# well-siting-meter.net
KiCad netlist of a schematic drawn in EAGLE
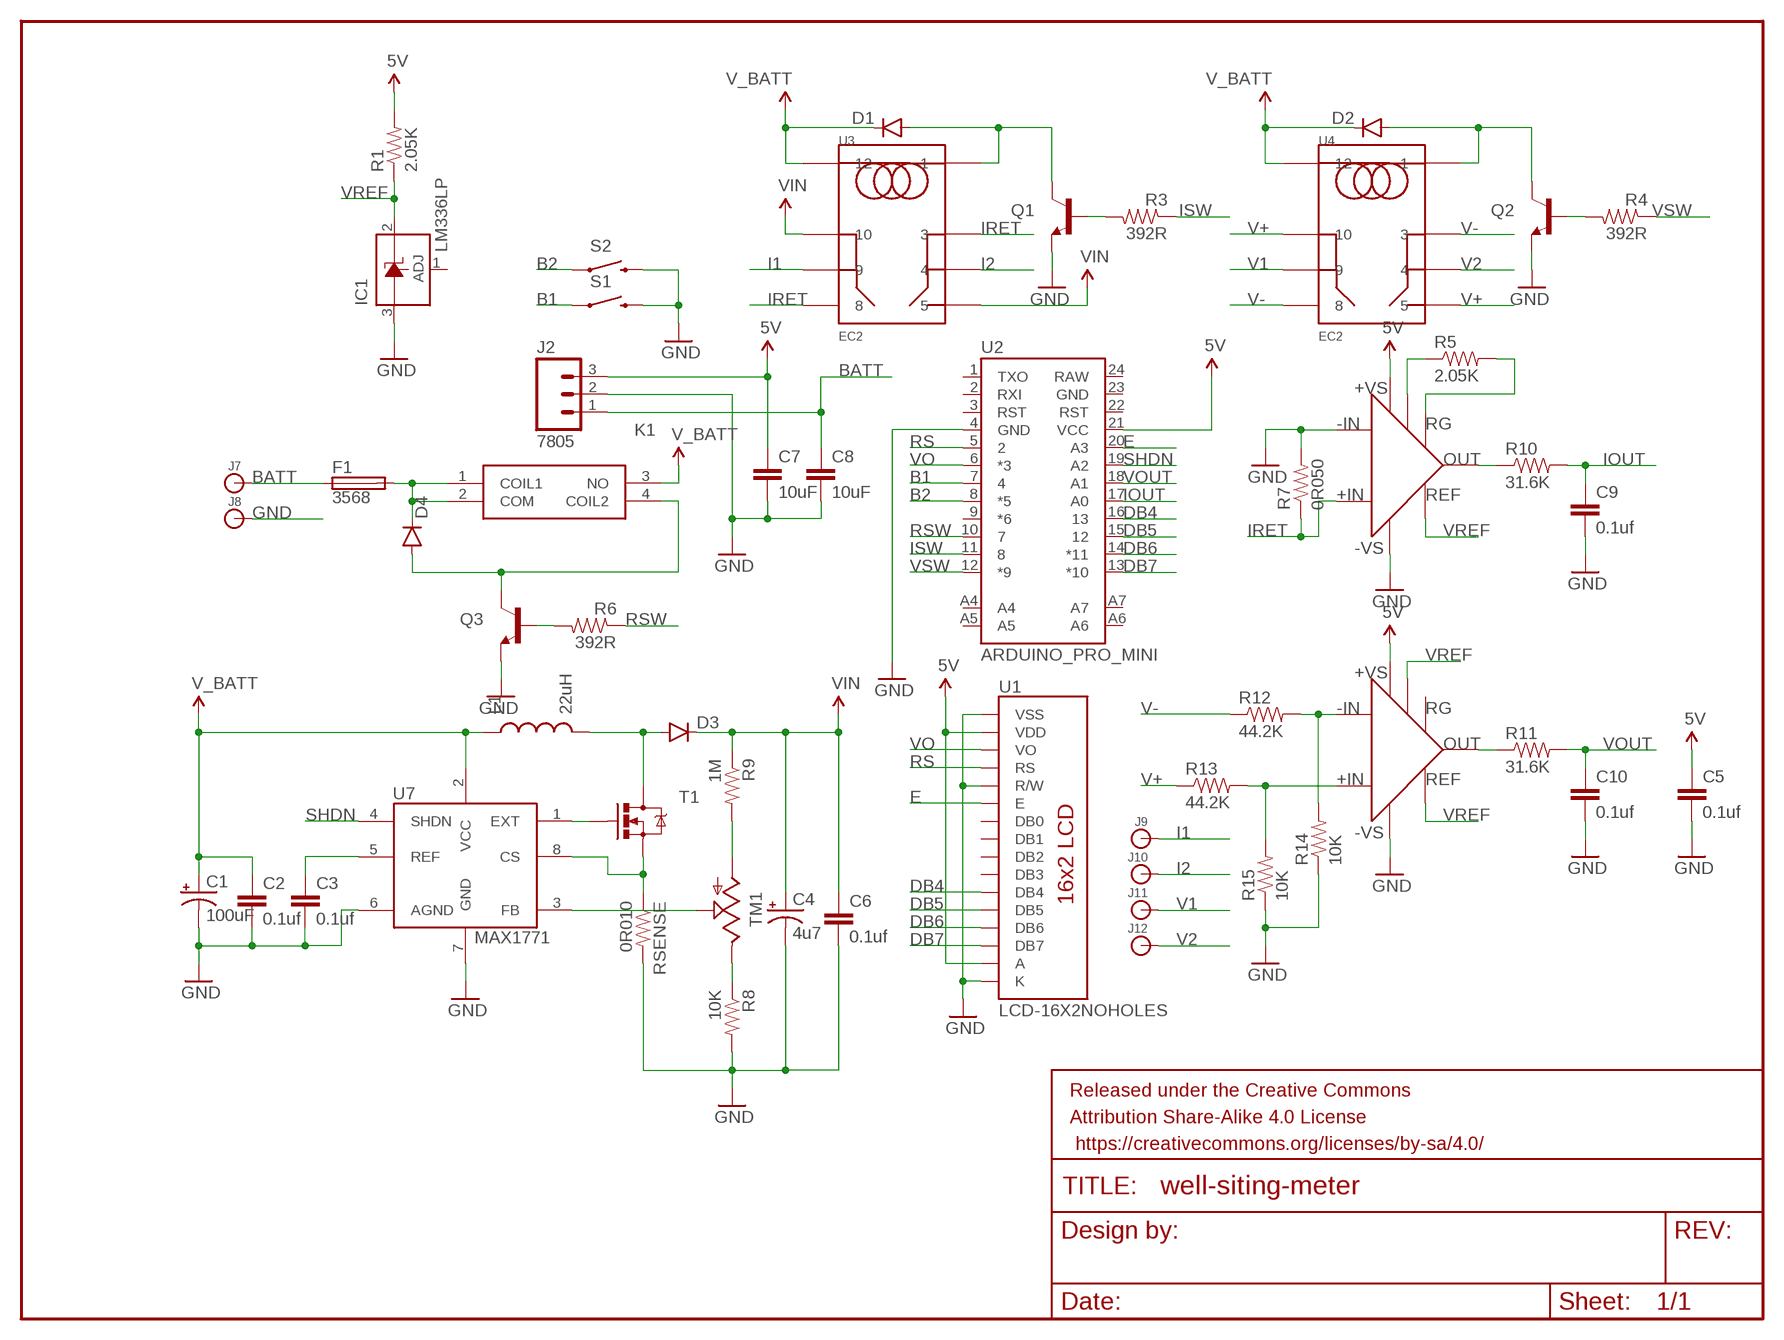
[diagram p0: schematic, sheet 1]

(export (version "E")
  (design (tool "Eeschema 10.0.6"))
  (components
    (comp (ref "C1")
      (value "100uF")
      (footprint "eagle-import:CPOL-RADIAL-1000UF-25V")
      (libsource (lib "eagle-import") (part "CAP_POLPTH4"))
    )
    (comp (ref "C2")
      (value "0.1uf")
      (footprint "eagle-import:CAP-PTH-5MM")
      (libsource (lib "eagle-import") (part "CAPPTH1"))
    )
    (comp (ref "C3")
      (value "0.1uf")
      (footprint "eagle-import:CAP-PTH-5MM")
      (libsource (lib "eagle-import") (part "CAPPTH1"))
    )
    (comp (ref "C4")
      (value "4u7")
      (footprint "eagle-import:CPOL-RADIAL-1000UF-25V")
      (libsource (lib "eagle-import") (part "CAP_POLPTH4"))
    )
    (comp (ref "C5")
      (value "0.1uf")
      (footprint "eagle-import:CAP-PTH-5MM")
      (libsource (lib "eagle-import") (part "CAPPTH1"))
    )
    (comp (ref "C6")
      (value "0.1uf")
      (footprint "eagle-import:CAP-PTH-5MM")
      (libsource (lib "eagle-import") (part "CAPPTH1"))
    )
    (comp (ref "C7")
      (value "10uF")
      (footprint "eagle-import:CAP-PTH-5MM")
      (libsource (lib "eagle-import") (part "CAPPTH1"))
    )
    (comp (ref "C8")
      (value "10uF")
      (footprint "eagle-import:CAP-PTH-5MM")
      (libsource (lib "eagle-import") (part "CAPPTH1"))
    )
    (comp (ref "C9")
      (value "0.1uf")
      (footprint "eagle-import:CAP-PTH-5MM")
      (libsource (lib "eagle-import") (part "CAPPTH1"))
    )
    (comp (ref "C10")
      (value "0.1uf")
      (footprint "eagle-import:CAP-PTH-5MM")
      (libsource (lib "eagle-import") (part "CAPPTH1"))
    )
    (comp (ref "D1")
      (value "DIODEPTH")
      (footprint "eagle-import:DIODE-1N4001")
      (libsource (lib "eagle-import") (part "DIODEPTH"))
    )
    (comp (ref "D2")
      (value "DIODEPTH")
      (footprint "eagle-import:DIODE-1N4001")
      (libsource (lib "eagle-import") (part "DIODEPTH"))
    )
    (comp (ref "D3")
      (value "DIODEPTH")
      (footprint "eagle-import:DIODE-1N4001")
      (libsource (lib "eagle-import") (part "DIODEPTH"))
    )
    (comp (ref "D4")
      (value "DIODEPTH")
      (footprint "eagle-import:DIODE-1N4001")
      (libsource (lib "eagle-import") (part "DIODEPTH"))
    )
    (comp (ref "F1")
      (value "3568")
      (footprint "eagle-import:3568")
      (libsource (lib "eagle-import") (part "3568"))
    )
    (comp (ref "FRAME1")
      (value "FRAME-LETTER")
      (footprint "eagle-import:CREATIVE_COMMONS")
      (libsource (lib "eagle-import") (part "FRAME-LETTER"))
    )
    (comp (ref "IC1")
      (value "LM336LP")
      (footprint "eagle-import:TO92")
      (libsource (lib "eagle-import") (part "LM336LP"))
    )
    (comp (ref "J2")
      (value "7805")
      (footprint "eagle-import:1X03")
      (libsource (lib "eagle-import") (part "M03PTH"))
    )
    (comp (ref "J7")
      (value "BANANA_CONN")
      (footprint "eagle-import:BANANA_CONN")
      (libsource (lib "eagle-import") (part "BANANA_CONN"))
    )
    (comp (ref "J8")
      (value "BANANA_CONN")
      (footprint "eagle-import:BANANA_CONN")
      (libsource (lib "eagle-import") (part "BANANA_CONN"))
    )
    (comp (ref "J9")
      (value "BANANA_CONN")
      (footprint "eagle-import:BANANA_CONN")
      (libsource (lib "eagle-import") (part "BANANA_CONN"))
    )
    (comp (ref "J10")
      (value "BANANA_CONN")
      (footprint "eagle-import:BANANA_CONN")
      (libsource (lib "eagle-import") (part "BANANA_CONN"))
    )
    (comp (ref "J11")
      (value "BANANA_CONN")
      (footprint "eagle-import:BANANA_CONN")
      (libsource (lib "eagle-import") (part "BANANA_CONN"))
    )
    (comp (ref "J12")
      (value "BANANA_CONN")
      (footprint "eagle-import:BANANA_CONN")
      (libsource (lib "eagle-import") (part "BANANA_CONN"))
    )
    (comp (ref "K1")
      (value "OJE-SH-105HM,000")
      (footprint "eagle-import:OJ-SH-124LMH")
      (fields (field (name "RS_PART_NUMBER") "1639319"))
      (libsource (lib "eagle-import") (part "OJE-SH-105HM,000"))
    )
    (comp (ref "L1")
      (value "22uH")
      (footprint "eagle-import:1415")
      (libsource (lib "eagle-import") (part "WE-FAMI"))
    )
    (comp (ref "Q1")
      (value "TRANSISTOR_NPNTO92")
      (footprint "eagle-import:TO-92")
      (libsource (lib "eagle-import") (part "TRANSISTOR_NPNTO92"))
    )
    (comp (ref "Q2")
      (value "TRANSISTOR_NPNTO92")
      (footprint "eagle-import:TO-92")
      (libsource (lib "eagle-import") (part "TRANSISTOR_NPNTO92"))
    )
    (comp (ref "Q3")
      (value "TRANSISTOR_NPNTO92")
      (footprint "eagle-import:TO-92")
      (libsource (lib "eagle-import") (part "TRANSISTOR_NPNTO92"))
    )
    (comp (ref "R1")
      (value "2.05K")
      (footprint "eagle-import:AXIAL-0.4")
      (libsource (lib "eagle-import") (part "RESISTORPTH-1/4W"))
    )
    (comp (ref "R3")
      (value "392R")
      (footprint "eagle-import:AXIAL-0.4")
      (libsource (lib "eagle-import") (part "RESISTORPTH-1/4W"))
    )
    (comp (ref "R4")
      (value "392R")
      (footprint "eagle-import:AXIAL-0.4")
      (libsource (lib "eagle-import") (part "RESISTORPTH-1/4W"))
    )
    (comp (ref "R5")
      (value "2.05K")
      (footprint "eagle-import:AXIAL-0.4")
      (libsource (lib "eagle-import") (part "RESISTORPTH-1/4W"))
    )
    (comp (ref "R6")
      (value "392R")
      (footprint "eagle-import:AXIAL-0.4")
      (libsource (lib "eagle-import") (part "RESISTORPTH-1/4W"))
    )
    (comp (ref "R7")
      (value "0R050")
      (footprint "eagle-import:AXIAL-0.6")
      (libsource (lib "eagle-import") (part "RESISTORPTH-1W"))
    )
    (comp (ref "R8")
      (value "10K")
      (footprint "eagle-import:AXIAL-0.4")
      (libsource (lib "eagle-import") (part "RESISTORPTH-1/4W"))
    )
    (comp (ref "R9")
      (value "1M")
      (footprint "eagle-import:AXIAL-0.4")
      (libsource (lib "eagle-import") (part "RESISTORPTH-1/4W"))
    )
    (comp (ref "R10")
      (value "31.6K")
      (footprint "eagle-import:AXIAL-0.4")
      (libsource (lib "eagle-import") (part "RESISTORPTH-1/4W"))
    )
    (comp (ref "R11")
      (value "31.6K")
      (footprint "eagle-import:AXIAL-0.4")
      (libsource (lib "eagle-import") (part "RESISTORPTH-1/4W"))
    )
    (comp (ref "R12")
      (value "44.2K")
      (footprint "eagle-import:AXIAL-0.4")
      (libsource (lib "eagle-import") (part "RESISTORPTH-1/4W"))
    )
    (comp (ref "R13")
      (value "44.2K")
      (footprint "eagle-import:AXIAL-0.4")
      (libsource (lib "eagle-import") (part "RESISTORPTH-1/4W"))
    )
    (comp (ref "R14")
      (value "10K")
      (footprint "eagle-import:AXIAL-0.4")
      (libsource (lib "eagle-import") (part "RESISTORPTH-1/4W"))
    )
    (comp (ref "R15")
      (value "10K")
      (footprint "eagle-import:AXIAL-0.4")
      (libsource (lib "eagle-import") (part "RESISTORPTH-1/4W"))
    )
    (comp (ref "RSENSE")
      (value "0R010")
      (footprint "eagle-import:AXIAL-0.6")
      (libsource (lib "eagle-import") (part "RESISTORPTH-1W"))
    )
    (comp (ref "S1")
      (value "SWITCH-MOMENTARY-2PTH")
      (footprint "eagle-import:TACTILE-PTH")
      (libsource (lib "eagle-import") (part "SWITCH-MOMENTARY-2PTH"))
    )
    (comp (ref "S2")
      (value "SWITCH-MOMENTARY-2PTH")
      (footprint "eagle-import:TACTILE-PTH")
      (libsource (lib "eagle-import") (part "SWITCH-MOMENTARY-2PTH"))
    )
    (comp (ref "T1")
      (value "MOSFET-NCHANNELFQP30N06L")
      (footprint "eagle-import:TO220V")
      (libsource (lib "eagle-import") (part "MOSFET-NCHANNELFQP30N06L"))
    )
    (comp (ref "TM1")
      (value "TRIM3386")
      (footprint "eagle-import:TRIM-3386")
      (libsource (lib "eagle-import") (part "TRIM3386"))
    )
    (comp (ref "U1")
      (value "LCD-16X2NOHOLES")
      (footprint "eagle-import:LCD-16X2_NOHOLES")
      (libsource (lib "eagle-import") (part "LCD-16X2NOHOLES"))
    )
    (comp (ref "U2")
      (value "ARDUINO_PRO_MINI")
      (footprint "eagle-import:ARDUINO_PRO_MINI")
      (libsource (lib "eagle-import") (part "ARDUINO_PRO_MINI"))
    )
    (comp (ref "U3")
      (value "EC2")
      (footprint "eagle-import:EC2")
      (libsource (lib "eagle-import") (part "EC2"))
    )
    (comp (ref "U4")
      (value "EC2")
      (footprint "eagle-import:EC2")
      (libsource (lib "eagle-import") (part "EC2"))
    )
    (comp (ref "U5")
      (value "AD623")
      (footprint "eagle-import:DIP08")
      (libsource (lib "eagle-import") (part "AD623"))
    )
    (comp (ref "U6")
      (value "AD629")
      (footprint "eagle-import:DIP08")
      (libsource (lib "eagle-import") (part "AD623"))
    )
    (comp (ref "U7")
      (value "MAX1771")
      (footprint "eagle-import:DIP-08")
      (libsource (lib "eagle-import") (part "MAX1771"))
    )
  )
  (nets
    (net (code "1") (name "/B1") (class "Default")
      (node (ref "S1") (pin "1") (pinfunction "1_1") (pintype "passive"))
      (node (ref "U2") (pin "7") (pinfunction "4_7") (pintype "bidirectional"))
    )
    (net (code "2") (name "/B2") (class "Default")
      (node (ref "S2") (pin "1") (pinfunction "1_1") (pintype "passive"))
      (node (ref "U2") (pin "8") (pinfunction "*5_8") (pintype "bidirectional"))
    )
    (net (code "3") (name "/BATT") (class "Default")
      (node (ref "C8") (pin "1") (pinfunction "1_1") (pintype "passive"))
      (node (ref "F1") (pin "1") (pinfunction "1_1") (pintype "passive"))
      (node (ref "F1") (pin "2") (pinfunction "1_2") (pintype "passive"))
      (node (ref "J2") (pin "1") (pinfunction "1_1") (pintype "passive"))
      (node (ref "J7") (pin "P$1") (pinfunction "1_P$1") (pintype "passive"))
    )
    (net (code "4") (name "/DB4") (class "Default")
      (node (ref "U1") (pin "11") (pinfunction "DB4_11") (pintype "bidirectional"))
      (node (ref "U2") (pin "16") (pinfunction "13_16") (pintype "bidirectional"))
    )
    (net (code "5") (name "/DB5") (class "Default")
      (node (ref "U1") (pin "12") (pinfunction "DB5_12") (pintype "bidirectional"))
      (node (ref "U2") (pin "15") (pinfunction "12_15") (pintype "bidirectional"))
    )
    (net (code "6") (name "/DB6") (class "Default")
      (node (ref "U1") (pin "13") (pinfunction "DB6_13") (pintype "bidirectional"))
      (node (ref "U2") (pin "14") (pinfunction "*11_14") (pintype "bidirectional"))
    )
    (net (code "7") (name "/DB7") (class "Default")
      (node (ref "U1") (pin "14") (pinfunction "DB7_14") (pintype "bidirectional"))
      (node (ref "U2") (pin "13") (pinfunction "*10_13") (pintype "bidirectional"))
    )
    (net (code "8") (name "/E") (class "Default")
      (node (ref "U1") (pin "6") (pinfunction "E_6") (pintype "input"))
      (node (ref "U2") (pin "20") (pinfunction "A3_20") (pintype "bidirectional"))
    )
    (net (code "9") (name "/I1") (class "Default")
      (node (ref "J9") (pin "P$1") (pinfunction "1_P$1") (pintype "passive"))
      (node (ref "U3") (pin "9") (pinfunction "9_9") (pintype "bidirectional"))
    )
    (net (code "10") (name "/I2") (class "Default")
      (node (ref "J10") (pin "P$1") (pinfunction "1_P$1") (pintype "passive"))
      (node (ref "U3") (pin "4") (pinfunction "4_4") (pintype "bidirectional"))
    )
    (net (code "11") (name "/IOUT") (class "Default")
      (node (ref "C9") (pin "1") (pinfunction "1_1") (pintype "passive"))
      (node (ref "R10") (pin "P$2") (pinfunction "2_P$2") (pintype "passive"))
      (node (ref "U2") (pin "17") (pinfunction "A0_17") (pintype "bidirectional"))
    )
    (net (code "12") (name "/IRET") (class "Default")
      (node (ref "R7") (pin "P$1") (pinfunction "1_P$1") (pintype "passive"))
      (node (ref "U3") (pin "3") (pinfunction "3_3") (pintype "bidirectional"))
      (node (ref "U3") (pin "8") (pinfunction "8_8") (pintype "bidirectional"))
      (node (ref "U5") (pin "3") (pinfunction "+IN_3") (pintype "bidirectional"))
    )
    (net (code "13") (name "/ISW") (class "Default")
      (node (ref "R3") (pin "P$1") (pinfunction "1_P$1") (pintype "passive"))
      (node (ref "U2") (pin "11") (pinfunction "8_11") (pintype "bidirectional"))
    )
    (net (code "14") (name "/RS") (class "Default")
      (node (ref "U1") (pin "4") (pinfunction "RS_4") (pintype "input"))
      (node (ref "U2") (pin "5") (pinfunction "2_5") (pintype "bidirectional"))
    )
    (net (code "15") (name "/RSW") (class "Default")
      (node (ref "R6") (pin "P$1") (pinfunction "1_P$1") (pintype "passive"))
      (node (ref "U2") (pin "10") (pinfunction "7_10") (pintype "bidirectional"))
    )
    (net (code "16") (name "/SHDN") (class "Default")
      (node (ref "U2") (pin "19") (pinfunction "A2_19") (pintype "bidirectional"))
      (node (ref "U7") (pin "4") (pinfunction "SHDN_4") (pintype "input"))
    )
    (net (code "17") (name "/V+") (class "Default")
      (node (ref "R13") (pin "P$1") (pinfunction "1_P$1") (pintype "passive"))
      (node (ref "U4") (pin "10") (pinfunction "10_10") (pintype "bidirectional"))
      (node (ref "U4") (pin "5") (pinfunction "5_5") (pintype "bidirectional"))
    )
    (net (code "18") (name "/V-") (class "Default")
      (node (ref "R12") (pin "P$1") (pinfunction "1_P$1") (pintype "passive"))
      (node (ref "U4") (pin "3") (pinfunction "3_3") (pintype "bidirectional"))
      (node (ref "U4") (pin "8") (pinfunction "8_8") (pintype "bidirectional"))
    )
    (net (code "19") (name "/V1") (class "Default")
      (node (ref "J11") (pin "P$1") (pinfunction "1_P$1") (pintype "passive"))
      (node (ref "U4") (pin "9") (pinfunction "9_9") (pintype "bidirectional"))
    )
    (net (code "20") (name "/V2") (class "Default")
      (node (ref "J12") (pin "P$1") (pinfunction "1_P$1") (pintype "passive"))
      (node (ref "U4") (pin "4") (pinfunction "4_4") (pintype "bidirectional"))
    )
    (net (code "21") (name "/VO") (class "Default")
      (node (ref "U1") (pin "3") (pinfunction "VO_3") (pintype "bidirectional"))
      (node (ref "U2") (pin "6") (pinfunction "*3_6") (pintype "bidirectional"))
    )
    (net (code "22") (name "/VOUT") (class "Default")
      (node (ref "C10") (pin "1") (pinfunction "1_1") (pintype "passive"))
      (node (ref "R11") (pin "P$2") (pinfunction "2_P$2") (pintype "passive"))
      (node (ref "U2") (pin "18") (pinfunction "A1_18") (pintype "bidirectional"))
    )
    (net (code "23") (name "/VREF") (class "Default")
      (node (ref "IC1") (pin "2") (pinfunction "C_2") (pintype "passive"))
      (node (ref "R1") (pin "P$1") (pinfunction "1_P$1") (pintype "passive"))
      (node (ref "U5") (pin "5") (pinfunction "REF_5") (pintype "bidirectional"))
      (node (ref "U6") (pin "1") (pinfunction "-RG_1") (pintype "bidirectional"))
      (node (ref "U6") (pin "5") (pinfunction "REF_5") (pintype "bidirectional"))
    )
    (net (code "24") (name "/VSW") (class "Default")
      (node (ref "R4") (pin "P$1") (pinfunction "1_P$1") (pintype "passive"))
      (node (ref "U2") (pin "12") (pinfunction "*9_12") (pintype "bidirectional"))
    )
    (net (code "25") (name "5V") (class "Default")
      (node (ref "C5") (pin "1") (pinfunction "1_1") (pintype "passive"))
      (node (ref "C7") (pin "1") (pinfunction "1_1") (pintype "passive"))
      (node (ref "J2") (pin "3") (pinfunction "3_3") (pintype "passive"))
      (node (ref "R1") (pin "P$2") (pinfunction "2_P$2") (pintype "passive"))
      (node (ref "U1") (pin "15") (pinfunction "A_15") (pintype "power_in"))
      (node (ref "U1") (pin "2") (pinfunction "VDD_2") (pintype "power_in"))
      (node (ref "U2") (pin "21") (pinfunction "VCC_21") (pintype "bidirectional"))
      (node (ref "U5") (pin "7") (pinfunction "+VS_7") (pintype "bidirectional"))
      (node (ref "U6") (pin "7") (pinfunction "+VS_7") (pintype "bidirectional"))
    )
    (net (code "26") (name "GND") (class "Default")
      (node (ref "C1") (pin "2") (pinfunction "-_2") (pintype "passive"))
      (node (ref "C10") (pin "2") (pinfunction "2_2") (pintype "passive"))
      (node (ref "C2") (pin "2") (pinfunction "2_2") (pintype "passive"))
      (node (ref "C3") (pin "2") (pinfunction "2_2") (pintype "passive"))
      (node (ref "C4") (pin "2") (pinfunction "-_2") (pintype "passive"))
      (node (ref "C5") (pin "2") (pinfunction "2_2") (pintype "passive"))
      (node (ref "C6") (pin "2") (pinfunction "2_2") (pintype "passive"))
      (node (ref "C7") (pin "2") (pinfunction "2_2") (pintype "passive"))
      (node (ref "C8") (pin "2") (pinfunction "2_2") (pintype "passive"))
      (node (ref "C9") (pin "2") (pinfunction "2_2") (pintype "passive"))
      (node (ref "IC1") (pin "3") (pinfunction "A_3") (pintype "input"))
      (node (ref "J2") (pin "2") (pinfunction "2_2") (pintype "passive"))
      (node (ref "J8") (pin "P$1") (pinfunction "1_P$1") (pintype "passive"))
      (node (ref "Q1") (pin "1") (pinfunction "E_1") (pintype "passive"))
      (node (ref "Q2") (pin "1") (pinfunction "E_1") (pintype "passive"))
      (node (ref "Q3") (pin "1") (pinfunction "E_1") (pintype "passive"))
      (node (ref "R14") (pin "P$1") (pinfunction "1_P$1") (pintype "passive"))
      (node (ref "R15") (pin "P$1") (pinfunction "1_P$1") (pintype "passive"))
      (node (ref "R7") (pin "P$2") (pinfunction "2_P$2") (pintype "passive"))
      (node (ref "R8") (pin "P$2") (pinfunction "2_P$2") (pintype "passive"))
      (node (ref "RSENSE") (pin "P$2") (pinfunction "2_P$2") (pintype "passive"))
      (node (ref "S1") (pin "3") (pinfunction "2_3") (pintype "passive"))
      (node (ref "S2") (pin "3") (pinfunction "2_3") (pintype "passive"))
      (node (ref "U1") (pin "1") (pinfunction "VSS_1") (pintype "power_in"))
      (node (ref "U1") (pin "16") (pinfunction "K_16") (pintype "power_in"))
      (node (ref "U1") (pin "5") (pinfunction "R/W_5") (pintype "input"))
      (node (ref "U2") (pin "4") (pinfunction "GND_4") (pintype "bidirectional"))
      (node (ref "U5") (pin "2") (pinfunction "-IN_2") (pintype "bidirectional"))
      (node (ref "U5") (pin "4") (pinfunction "-VS_4") (pintype "bidirectional"))
      (node (ref "U6") (pin "4") (pinfunction "-VS_4") (pintype "bidirectional"))
      (node (ref "U7") (pin "6") (pinfunction "AGND_6") (pintype "input"))
      (node (ref "U7") (pin "7") (pinfunction "GND_7") (pintype "input"))
    )
    (net (code "27") (name "Net-(K1-COIL1)") (class "Default")
      (node (ref "D4") (pin "C") (pinfunction "C_C") (pintype "passive"))
      (node (ref "F1") (pin "3") (pinfunction "2_3") (pintype "passive"))
      (node (ref "F1") (pin "4") (pinfunction "2_4") (pintype "passive"))
      (node (ref "K1") (pin "1") (pinfunction "COIL1_1") (pintype "bidirectional"))
      (node (ref "K1") (pin "2") (pinfunction "COM_2") (pintype "bidirectional"))
    )
    (net (code "28") (name "Net-(K1-COIL2)") (class "Default")
      (node (ref "D4") (pin "A") (pinfunction "A_A") (pintype "passive"))
      (node (ref "K1") (pin "4") (pinfunction "COIL2_4") (pintype "bidirectional"))
      (node (ref "Q3") (pin "3") (pinfunction "C_3") (pintype "passive"))
    )
    (net (code "29") (name "Net-(L1-2)") (class "Default")
      (node (ref "D3") (pin "A") (pinfunction "A_A") (pintype "passive"))
      (node (ref "L1") (pin "P2") (pinfunction "2_P2") (pintype "passive"))
      (node (ref "T1") (pin "2") (pinfunction "D_2") (pintype "passive"))
    )
    (net (code "30") (name "Net-(Q1-B)") (class "Default")
      (node (ref "Q1") (pin "2") (pinfunction "B_2") (pintype "passive"))
      (node (ref "R3") (pin "P$2") (pinfunction "2_P$2") (pintype "passive"))
    )
    (net (code "31") (name "Net-(Q1-C)") (class "Default")
      (node (ref "D1") (pin "A") (pinfunction "A_A") (pintype "passive"))
      (node (ref "Q1") (pin "3") (pinfunction "C_3") (pintype "passive"))
      (node (ref "U3") (pin "1") (pinfunction "1_1") (pintype "bidirectional"))
    )
    (net (code "32") (name "Net-(Q2-B)") (class "Default")
      (node (ref "Q2") (pin "2") (pinfunction "B_2") (pintype "passive"))
      (node (ref "R4") (pin "P$2") (pinfunction "2_P$2") (pintype "passive"))
    )
    (net (code "33") (name "Net-(Q2-C)") (class "Default")
      (node (ref "D2") (pin "A") (pinfunction "A_A") (pintype "passive"))
      (node (ref "Q2") (pin "3") (pinfunction "C_3") (pintype "passive"))
      (node (ref "U4") (pin "1") (pinfunction "1_1") (pintype "bidirectional"))
    )
    (net (code "34") (name "Net-(Q3-B)") (class "Default")
      (node (ref "Q3") (pin "2") (pinfunction "B_2") (pintype "passive"))
      (node (ref "R6") (pin "P$2") (pinfunction "2_P$2") (pintype "passive"))
    )
    (net (code "35") (name "Net-(R5-1)") (class "Default")
      (node (ref "R5") (pin "P$1") (pinfunction "1_P$1") (pintype "passive"))
      (node (ref "U5") (pin "1") (pinfunction "-RG_1") (pintype "bidirectional"))
    )
    (net (code "36") (name "Net-(R5-2)") (class "Default")
      (node (ref "R5") (pin "P$2") (pinfunction "2_P$2") (pintype "passive"))
      (node (ref "U5") (pin "8") (pinfunction "+RG_8") (pintype "bidirectional"))
    )
    (net (code "37") (name "Net-(R8-1)") (class "Default")
      (node (ref "R8") (pin "P$1") (pinfunction "1_P$1") (pintype "passive"))
      (node (ref "TM1") (pin "1") (pinfunction "E_1") (pintype "passive"))
    )
    (net (code "38") (name "Net-(R9-2)") (class "Default")
      (node (ref "R9") (pin "P$2") (pinfunction "2_P$2") (pintype "passive"))
      (node (ref "TM1") (pin "3") (pinfunction "A_3") (pintype "passive"))
    )
    (net (code "39") (name "Net-(R10-1)") (class "Default")
      (node (ref "R10") (pin "P$1") (pinfunction "1_P$1") (pintype "passive"))
      (node (ref "U5") (pin "6") (pinfunction "OUT_6") (pintype "bidirectional"))
    )
    (net (code "40") (name "Net-(R11-1)") (class "Default")
      (node (ref "R11") (pin "P$1") (pinfunction "1_P$1") (pintype "passive"))
      (node (ref "U6") (pin "6") (pinfunction "OUT_6") (pintype "bidirectional"))
    )
    (net (code "41") (name "Net-(R12-2)") (class "Default")
      (node (ref "R12") (pin "P$2") (pinfunction "2_P$2") (pintype "passive"))
      (node (ref "R14") (pin "P$2") (pinfunction "2_P$2") (pintype "passive"))
      (node (ref "U6") (pin "2") (pinfunction "-IN_2") (pintype "bidirectional"))
    )
    (net (code "42") (name "Net-(R13-2)") (class "Default")
      (node (ref "R13") (pin "P$2") (pinfunction "2_P$2") (pintype "passive"))
      (node (ref "R15") (pin "P$2") (pinfunction "2_P$2") (pintype "passive"))
      (node (ref "U6") (pin "3") (pinfunction "+IN_3") (pintype "bidirectional"))
    )
    (net (code "43") (name "Net-(RSENSE-1)") (class "Default")
      (node (ref "RSENSE") (pin "P$1") (pinfunction "1_P$1") (pintype "passive"))
      (node (ref "T1") (pin "3") (pinfunction "S_3") (pintype "passive"))
      (node (ref "U7") (pin "8") (pinfunction "CS_8") (pintype "input"))
    )
    (net (code "44") (name "Net-(T1-G)") (class "Default")
      (node (ref "T1") (pin "1") (pinfunction "G_1") (pintype "passive"))
      (node (ref "U7") (pin "1") (pinfunction "EXT_1") (pintype "output"))
    )
    (net (code "45") (name "Net-(TM1-S)") (class "Default")
      (node (ref "TM1") (pin "2") (pinfunction "S_2") (pintype "passive"))
      (node (ref "U7") (pin "3") (pinfunction "FB_3") (pintype "input"))
    )
    (net (code "46") (name "Net-(U7-REF)") (class "Default")
      (node (ref "C3") (pin "1") (pinfunction "1_1") (pintype "passive"))
      (node (ref "U7") (pin "5") (pinfunction "REF_5") (pintype "input"))
    )
    (net (code "47") (name "VIN") (class "Default")
      (node (ref "C4") (pin "1") (pinfunction "+_1") (pintype "passive"))
      (node (ref "C6") (pin "1") (pinfunction "1_1") (pintype "passive"))
      (node (ref "D3") (pin "C") (pinfunction "C_C") (pintype "passive"))
      (node (ref "R9") (pin "P$1") (pinfunction "1_P$1") (pintype "passive"))
      (node (ref "U3") (pin "10") (pinfunction "10_10") (pintype "bidirectional"))
      (node (ref "U3") (pin "5") (pinfunction "5_5") (pintype "bidirectional"))
    )
    (net (code "48") (name "V_BATT") (class "Default")
      (node (ref "C1") (pin "1") (pinfunction "+_1") (pintype "passive"))
      (node (ref "C2") (pin "1") (pinfunction "1_1") (pintype "passive"))
      (node (ref "D1") (pin "C") (pinfunction "C_C") (pintype "passive"))
      (node (ref "D2") (pin "C") (pinfunction "C_C") (pintype "passive"))
      (node (ref "K1") (pin "3") (pinfunction "NO_3") (pintype "bidirectional"))
      (node (ref "L1") (pin "P1") (pinfunction "1_P1") (pintype "passive"))
      (node (ref "U3") (pin "12") (pinfunction "12_12") (pintype "bidirectional"))
      (node (ref "U4") (pin "12") (pinfunction "12_12") (pintype "bidirectional"))
      (node (ref "U7") (pin "2") (pinfunction "VCC_2") (pintype "input"))
    )
    (net (code "49") (name "unconnected-(IC1-ADJ-Pad1)") (class "Default")
      (node (ref "IC1") (pin "1") (pinfunction "ADJ_1") (pintype "input"))
    )
    (net (code "50") (name "unconnected-(U1-DB0-Pad7)") (class "Default")
      (node (ref "U1") (pin "7") (pinfunction "DB0_7") (pintype "bidirectional"))
    )
    (net (code "51") (name "unconnected-(U1-DB1-Pad8)") (class "Default")
      (node (ref "U1") (pin "8") (pinfunction "DB1_8") (pintype "bidirectional"))
    )
    (net (code "52") (name "unconnected-(U1-DB2-Pad9)") (class "Default")
      (node (ref "U1") (pin "9") (pinfunction "DB2_9") (pintype "bidirectional"))
    )
    (net (code "53") (name "unconnected-(U1-DB3-Pad10)") (class "Default")
      (node (ref "U1") (pin "10") (pinfunction "DB3_10") (pintype "bidirectional"))
    )
    (net (code "54") (name "unconnected-(U2-*6-Pad9)") (class "Default")
      (node (ref "U2") (pin "9") (pinfunction "*6_9") (pintype "bidirectional"))
    )
    (net (code "55") (name "unconnected-(U2-GND-Pad23)") (class "Default")
      (node (ref "U2") (pin "23") (pinfunction "GND_23") (pintype "bidirectional"))
    )
    (net (code "56") (name "unconnected-(U2-PadA4)") (class "Default")
      (node (ref "U2") (pin "A4") (pinfunction "A4_A4") (pintype "bidirectional"))
    )
    (net (code "57") (name "unconnected-(U2-PadA5)") (class "Default")
      (node (ref "U2") (pin "A5") (pinfunction "A5_A5") (pintype "bidirectional"))
    )
    (net (code "58") (name "unconnected-(U2-PadA6)") (class "Default")
      (node (ref "U2") (pin "A6") (pinfunction "A6_A6") (pintype "bidirectional"))
    )
    (net (code "59") (name "unconnected-(U2-PadA7)") (class "Default")
      (node (ref "U2") (pin "A7") (pinfunction "A7_A7") (pintype "bidirectional"))
    )
    (net (code "60") (name "unconnected-(U2-RAW-Pad24)") (class "Default")
      (node (ref "U2") (pin "24") (pinfunction "RAW_24") (pintype "bidirectional"))
    )
    (net (code "61") (name "unconnected-(U2-RST-Pad3)") (class "Default")
      (node (ref "U2") (pin "3") (pinfunction "RST_3") (pintype "bidirectional"))
    )
    (net (code "62") (name "unconnected-(U2-RST-Pad22)") (class "Default")
      (node (ref "U2") (pin "22") (pinfunction "RST_22") (pintype "bidirectional"))
    )
    (net (code "63") (name "unconnected-(U2-RXI-Pad2)") (class "Default")
      (node (ref "U2") (pin "2") (pinfunction "RXI_2") (pintype "bidirectional"))
    )
    (net (code "64") (name "unconnected-(U2-TXO-Pad1)") (class "Default")
      (node (ref "U2") (pin "1") (pinfunction "TXO_1") (pintype "bidirectional"))
    )
    (net (code "65") (name "unconnected-(U6-+RG-Pad8)") (class "Default")
      (node (ref "U6") (pin "8") (pinfunction "+RG_8") (pintype "bidirectional"))
    )
  )
)
